# HeadAmp1.net
KiCad netlist of a schematic drawn in EAGLE
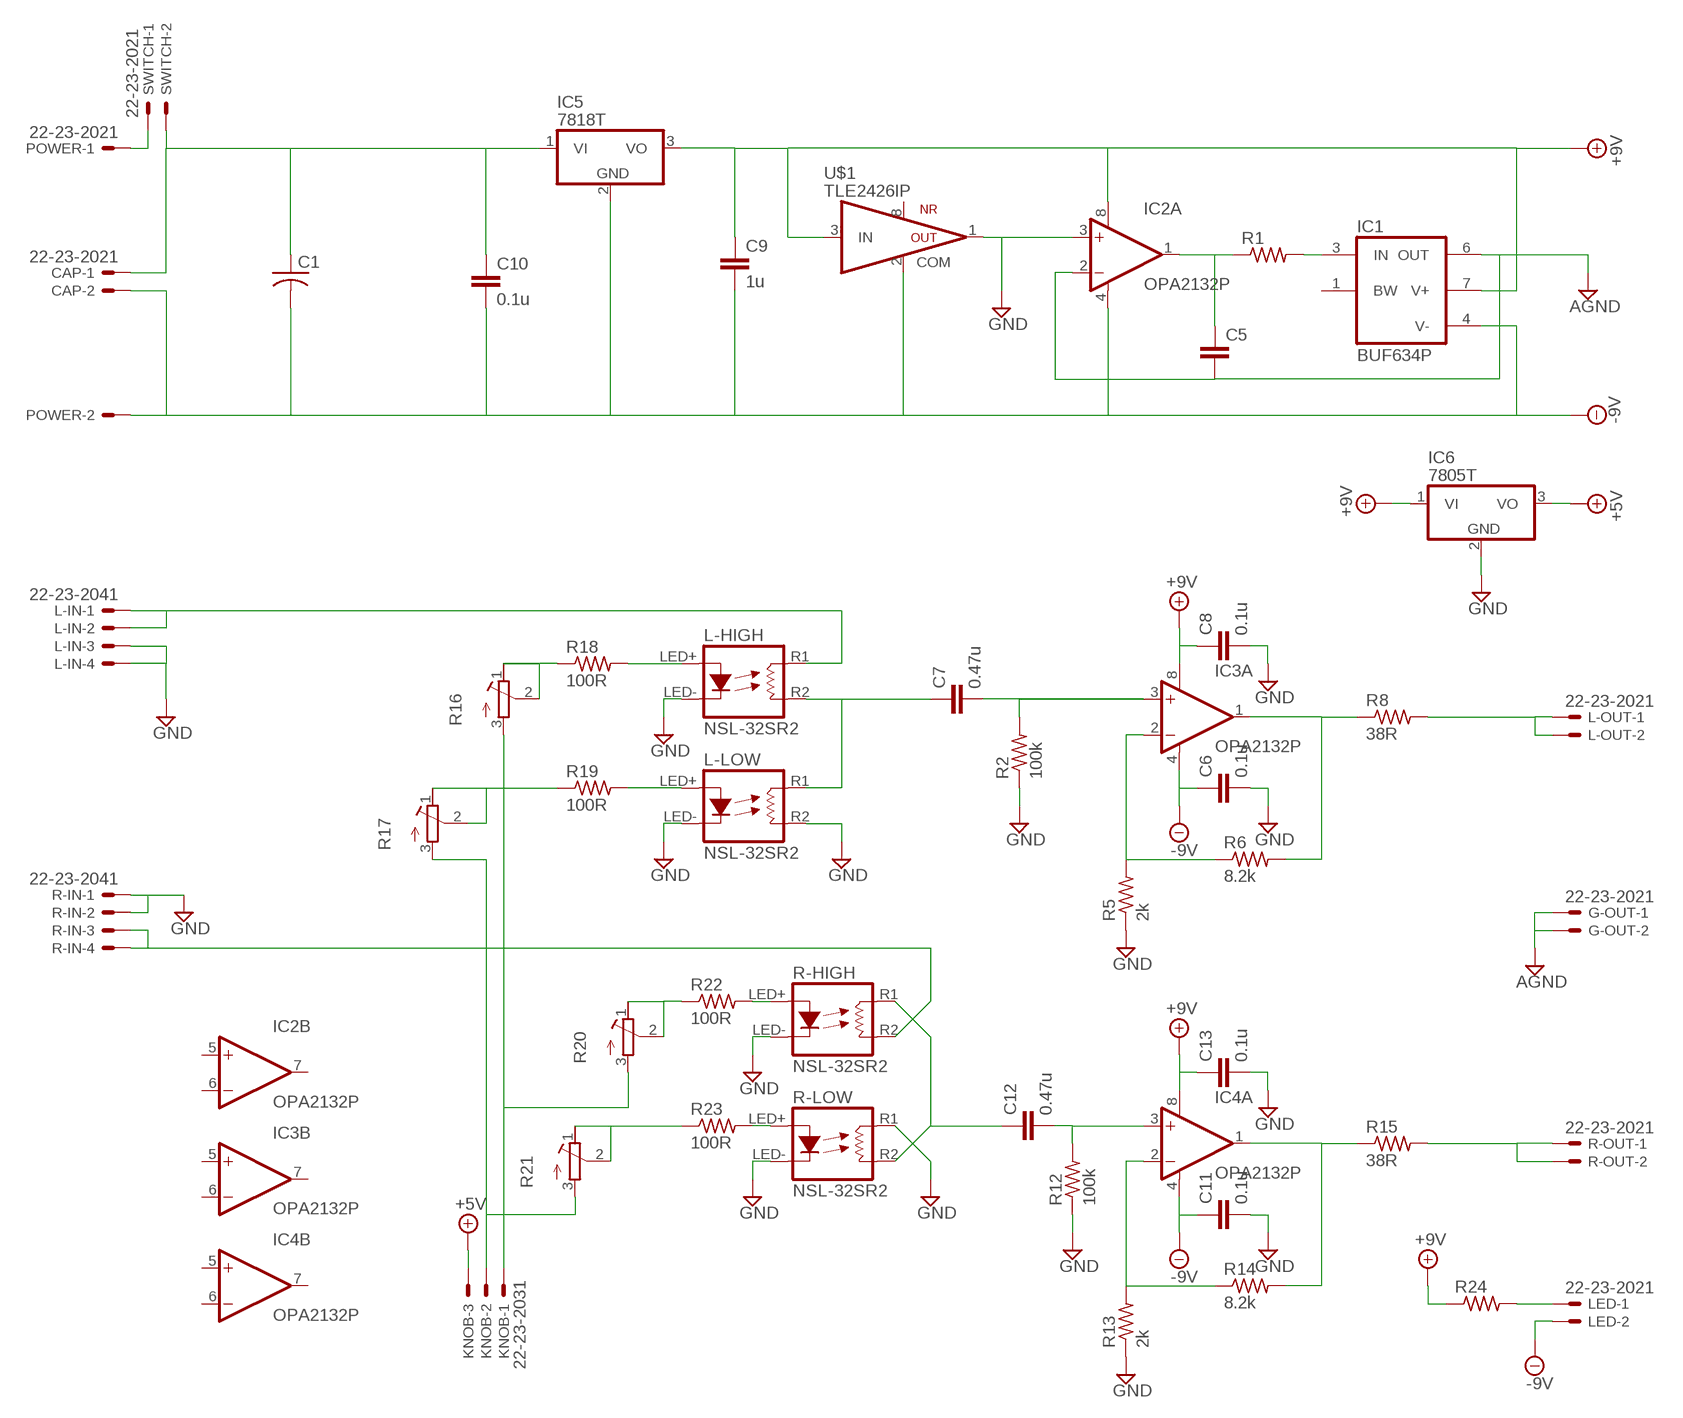
[diagram p0: schematic, sheet 1]

(export (version "E")
  (design (tool "Eeschema 10.0.6"))
  (components
    (comp (ref "C1")
      (value "C-US050-075X075")
      (footprint "eagle-import:C050-075X075")
      (libsource (lib "eagle-import") (part "C-US050-075X075"))
    )
    (comp (ref "C5")
      (value "C5/3")
      (footprint "eagle-import:C5B3")
      (libsource (lib "eagle-import") (part "C5/3"))
    )
    (comp (ref "C6")
      (value "0.1u")
      (footprint "eagle-import:C5B3")
      (libsource (lib "eagle-import") (part "C5/3"))
    )
    (comp (ref "C7")
      (value "0.47u")
      (footprint "eagle-import:C5B3")
      (libsource (lib "eagle-import") (part "C5/3"))
    )
    (comp (ref "C8")
      (value "0.1u")
      (footprint "eagle-import:C5B3")
      (libsource (lib "eagle-import") (part "C5/3"))
    )
    (comp (ref "C9")
      (value "1u")
      (footprint "eagle-import:C5B3")
      (libsource (lib "eagle-import") (part "C5/3"))
    )
    (comp (ref "C10")
      (value "0.1u")
      (footprint "eagle-import:C5B3")
      (libsource (lib "eagle-import") (part "C5/3"))
    )
    (comp (ref "C11")
      (value "0.1u")
      (footprint "eagle-import:C5B3")
      (libsource (lib "eagle-import") (part "C5/3"))
    )
    (comp (ref "C12")
      (value "0.47u")
      (footprint "eagle-import:C5B3")
      (libsource (lib "eagle-import") (part "C5/3"))
    )
    (comp (ref "C13")
      (value "0.1u")
      (footprint "eagle-import:C5B3")
      (libsource (lib "eagle-import") (part "C5/3"))
    )
    (comp (ref "CAP")
      (value "22-23-2021")
      (footprint "eagle-import:22-23-2021")
      (fields (field (name "MF") "MOLEX"))
      (libsource (lib "eagle-import") (part "22-23-2021"))
    )
    (comp (ref "G-OUT")
      (value "22-23-2021")
      (footprint "eagle-import:22-23-2021")
      (fields (field (name "MF") "MOLEX"))
      (libsource (lib "eagle-import") (part "22-23-2021"))
    )
    (comp (ref "IC1")
      (value "BUF634P")
      (footprint "eagle-import:DIL08")
      (fields (field (name "MF") "TEXAS INSTRUMENTS"))
      (libsource (lib "eagle-import") (part "BUF634P"))
    )
    (comp (ref "IC2")
      (value "OPA2132P")
      (footprint "eagle-import:DIL08")
      (libsource (lib "eagle-import") (part "OPA2132P"))
    )
    (comp (ref "IC3")
      (value "OPA2132P")
      (footprint "eagle-import:DIL08")
      (libsource (lib "eagle-import") (part "OPA2132P"))
    )
    (comp (ref "IC4")
      (value "OPA2132P")
      (footprint "eagle-import:DIL08")
      (libsource (lib "eagle-import") (part "OPA2132P"))
    )
    (comp (ref "IC5")
      (value "7818T")
      (footprint "eagle-import:TO220H")
      (libsource (lib "eagle-import") (part "78T18"))
    )
    (comp (ref "IC6")
      (value "7805T")
      (footprint "eagle-import:TO220H")
      (libsource (lib "eagle-import") (part "78T05"))
    )
    (comp (ref "KNOB")
      (value "22-23-2031")
      (footprint "eagle-import:22-23-2031")
      (fields (field (name "MF") "MOLEX"))
      (libsource (lib "eagle-import") (part "22-23-2031"))
    )
    (comp (ref "L-HIGH")
      (value "NSL-32SR2")
      (footprint "eagle-import:OPTO_32SR")
      (libsource (lib "eagle-import") (part "NSL-32SR2"))
    )
    (comp (ref "L-IN")
      (value "22-23-2041")
      (footprint "eagle-import:22-23-2041")
      (fields (field (name "MF") "MOLEX"))
      (libsource (lib "eagle-import") (part "22-23-2041"))
    )
    (comp (ref "L-LOW")
      (value "NSL-32SR2")
      (footprint "eagle-import:OPTO_32SR")
      (libsource (lib "eagle-import") (part "NSL-32SR2"))
    )
    (comp (ref "L-OUT")
      (value "22-23-2021")
      (footprint "eagle-import:22-23-2021")
      (fields (field (name "MF") "MOLEX"))
      (libsource (lib "eagle-import") (part "22-23-2021"))
    )
    (comp (ref "LED")
      (value "22-23-2021")
      (footprint "eagle-import:22-23-2021")
      (fields (field (name "MF") "MOLEX"))
      (libsource (lib "eagle-import") (part "22-23-2021"))
    )
    (comp (ref "POWER")
      (value "22-23-2021")
      (footprint "eagle-import:22-23-2021")
      (fields (field (name "MF") "MOLEX"))
      (libsource (lib "eagle-import") (part "22-23-2021"))
    )
    (comp (ref "R-HIGH")
      (value "NSL-32SR2")
      (footprint "eagle-import:OPTO_32SR")
      (libsource (lib "eagle-import") (part "NSL-32SR2"))
    )
    (comp (ref "R-IN")
      (value "22-23-2041")
      (footprint "eagle-import:22-23-2041")
      (fields (field (name "MF") "MOLEX"))
      (libsource (lib "eagle-import") (part "22-23-2041"))
    )
    (comp (ref "R-LOW")
      (value "NSL-32SR2")
      (footprint "eagle-import:OPTO_32SR")
      (libsource (lib "eagle-import") (part "NSL-32SR2"))
    )
    (comp (ref "R-OUT")
      (value "22-23-2021")
      (footprint "eagle-import:22-23-2021")
      (fields (field (name "MF") "MOLEX"))
      (libsource (lib "eagle-import") (part "22-23-2021"))
    )
    (comp (ref "R1")
      (value "R-US_0207/10")
      (footprint "eagle-import:0207_10")
      (libsource (lib "eagle-import") (part "R-US_0207/10"))
    )
    (comp (ref "R2")
      (value "100k")
      (footprint "eagle-import:0207_10")
      (libsource (lib "eagle-import") (part "R-US_0207/10"))
    )
    (comp (ref "R5")
      (value "2k")
      (footprint "eagle-import:0207_10")
      (libsource (lib "eagle-import") (part "R-US_0207/10"))
    )
    (comp (ref "R6")
      (value "8.2k")
      (footprint "eagle-import:0207_10")
      (libsource (lib "eagle-import") (part "R-US_0207/10"))
    )
    (comp (ref "R8")
      (value "38R")
      (footprint "eagle-import:0207_10")
      (libsource (lib "eagle-import") (part "R-US_0207/10"))
    )
    (comp (ref "R12")
      (value "100k")
      (footprint "eagle-import:0207_10")
      (libsource (lib "eagle-import") (part "R-US_0207/10"))
    )
    (comp (ref "R13")
      (value "2k")
      (footprint "eagle-import:0207_10")
      (libsource (lib "eagle-import") (part "R-US_0207/10"))
    )
    (comp (ref "R14")
      (value "8.2k")
      (footprint "eagle-import:0207_10")
      (libsource (lib "eagle-import") (part "R-US_0207/10"))
    )
    (comp (ref "R15")
      (value "38R")
      (footprint "eagle-import:0207_10")
      (libsource (lib "eagle-import") (part "R-US_0207/10"))
    )
    (comp (ref "R16")
      (value "R-TRIMMT93YB")
      (footprint "eagle-import:RTRIMT93YB")
      (libsource (lib "eagle-import") (part "R-TRIMMT93YB"))
    )
    (comp (ref "R17")
      (value "R-TRIMMT93YB")
      (footprint "eagle-import:RTRIMT93YB")
      (libsource (lib "eagle-import") (part "R-TRIMMT93YB"))
    )
    (comp (ref "R18")
      (value "100R")
      (footprint "eagle-import:0207_10")
      (libsource (lib "eagle-import") (part "R-US_0207/10"))
    )
    (comp (ref "R19")
      (value "100R")
      (footprint "eagle-import:0207_10")
      (libsource (lib "eagle-import") (part "R-US_0207/10"))
    )
    (comp (ref "R20")
      (value "R-TRIMMT93YB")
      (footprint "eagle-import:RTRIMT93YB")
      (libsource (lib "eagle-import") (part "R-TRIMMT93YB"))
    )
    (comp (ref "R21")
      (value "R-TRIMMT93YB")
      (footprint "eagle-import:RTRIMT93YB")
      (libsource (lib "eagle-import") (part "R-TRIMMT93YB"))
    )
    (comp (ref "R22")
      (value "100R")
      (footprint "eagle-import:0207_10")
      (libsource (lib "eagle-import") (part "R-US_0207/10"))
    )
    (comp (ref "R23")
      (value "100R")
      (footprint "eagle-import:0207_10")
      (libsource (lib "eagle-import") (part "R-US_0207/10"))
    )
    (comp (ref "R24")
      (value "R-US_0207/10")
      (footprint "eagle-import:0207_10")
      (libsource (lib "eagle-import") (part "R-US_0207/10"))
    )
    (comp (ref "SWITCH")
      (value "22-23-2021")
      (footprint "eagle-import:22-23-2021")
      (fields (field (name "MF") "MOLEX"))
      (libsource (lib "eagle-import") (part "22-23-2021"))
    )
    (comp (ref "U$1")
      (value "TLE2426IP")
      (footprint "eagle-import:DIL08")
      (libsource (lib "eagle-import") (part "TLE2426IP"))
    )
  )
  (nets
    (net (code "1") (name "+5V") (class "Default")
      (node (ref "IC6") (pin "3") (pinfunction "VO_3") (pintype "passive"))
      (node (ref "KNOB") (pin "3") (pinfunction "S_3") (pintype "passive"))
    )
    (net (code "2") (name "+9V") (class "Default")
      (node (ref "C13") (pin "1") (pinfunction "1_1") (pintype "passive"))
      (node (ref "C8") (pin "1") (pinfunction "1_1") (pintype "passive"))
      (node (ref "C9") (pin "1") (pinfunction "1_1") (pintype "passive"))
      (node (ref "IC1") (pin "7") (pinfunction "V+_7") (pintype "power_in"))
      (node (ref "IC2") (pin "8") (pinfunction "V+_8") (pintype "power_in"))
      (node (ref "IC3") (pin "8") (pinfunction "V+_8") (pintype "power_in"))
      (node (ref "IC4") (pin "8") (pinfunction "V+_8") (pintype "power_in"))
      (node (ref "IC5") (pin "3") (pinfunction "VO_3") (pintype "passive"))
      (node (ref "IC6") (pin "1") (pinfunction "VI_1") (pintype "input"))
      (node (ref "R24") (pin "1") (pinfunction "1_1") (pintype "passive"))
      (node (ref "U$1") (pin "3") (pinfunction "IN_3") (pintype "input"))
    )
    (net (code "3") (name "-9V") (class "Default")
      (node (ref "C1") (pin "2") (pinfunction "2_2") (pintype "passive"))
      (node (ref "C10") (pin "2") (pinfunction "2_2") (pintype "passive"))
      (node (ref "C11") (pin "1") (pinfunction "1_1") (pintype "passive"))
      (node (ref "C6") (pin "1") (pinfunction "1_1") (pintype "passive"))
      (node (ref "C9") (pin "2") (pinfunction "2_2") (pintype "passive"))
      (node (ref "CAP") (pin "2") (pinfunction "S_2") (pintype "passive"))
      (node (ref "IC1") (pin "4") (pinfunction "V-_4") (pintype "power_in"))
      (node (ref "IC2") (pin "4") (pinfunction "V-_4") (pintype "power_in"))
      (node (ref "IC3") (pin "4") (pinfunction "V-_4") (pintype "power_in"))
      (node (ref "IC4") (pin "4") (pinfunction "V-_4") (pintype "power_in"))
      (node (ref "IC5") (pin "2") (pinfunction "GND_2") (pintype "passive"))
      (node (ref "LED") (pin "2") (pinfunction "S_2") (pintype "passive"))
      (node (ref "POWER") (pin "2") (pinfunction "S_2") (pintype "passive"))
      (node (ref "U$1") (pin "2") (pinfunction "COMMON_2") (pintype "passive"))
    )
    (net (code "4") (name "AGND") (class "Default")
      (node (ref "C5") (pin "2") (pinfunction "2_2") (pintype "passive"))
      (node (ref "G-OUT") (pin "1") (pinfunction "S_1") (pintype "passive"))
      (node (ref "G-OUT") (pin "2") (pinfunction "S_2") (pintype "passive"))
      (node (ref "IC1") (pin "6") (pinfunction "OUT_6") (pintype "output"))
      (node (ref "IC2") (pin "2") (pinfunction "-IN_2") (pintype "input"))
    )
    (net (code "5") (name "GND") (class "Default")
      (node (ref "C11") (pin "2") (pinfunction "2_2") (pintype "passive"))
      (node (ref "C13") (pin "2") (pinfunction "2_2") (pintype "passive"))
      (node (ref "C6") (pin "2") (pinfunction "2_2") (pintype "passive"))
      (node (ref "C8") (pin "2") (pinfunction "2_2") (pintype "passive"))
      (node (ref "IC2") (pin "3") (pinfunction "+IN_3") (pintype "input"))
      (node (ref "IC6") (pin "2") (pinfunction "GND_2") (pintype "passive"))
      (node (ref "L-HIGH") (pin "LED-") (pinfunction "C_LED-") (pintype "passive"))
      (node (ref "L-IN") (pin "3") (pinfunction "S_3") (pintype "passive"))
      (node (ref "L-IN") (pin "4") (pinfunction "S_4") (pintype "passive"))
      (node (ref "L-LOW") (pin "LED-") (pinfunction "C_LED-") (pintype "passive"))
      (node (ref "L-LOW") (pin "R2") (pinfunction "L2_R2") (pintype "passive"))
      (node (ref "R-HIGH") (pin "LED-") (pinfunction "C_LED-") (pintype "passive"))
      (node (ref "R-IN") (pin "1") (pinfunction "S_1") (pintype "passive"))
      (node (ref "R-IN") (pin "2") (pinfunction "S_2") (pintype "passive"))
      (node (ref "R-LOW") (pin "LED-") (pinfunction "C_LED-") (pintype "passive"))
      (node (ref "R-LOW") (pin "R1") (pinfunction "L1_R1") (pintype "passive"))
      (node (ref "R12") (pin "1") (pinfunction "1_1") (pintype "passive"))
      (node (ref "R13") (pin "1") (pinfunction "1_1") (pintype "passive"))
      (node (ref "R2") (pin "1") (pinfunction "1_1") (pintype "passive"))
      (node (ref "R5") (pin "1") (pinfunction "1_1") (pintype "passive"))
      (node (ref "U$1") (pin "1") (pinfunction "OUT_1") (pintype "passive"))
    )
    (net (code "6") (name "Net-(CAPA-S)") (class "Default")
      (node (ref "C1") (pin "1") (pinfunction "1_1") (pintype "passive"))
      (node (ref "C10") (pin "1") (pinfunction "1_1") (pintype "passive"))
      (node (ref "CAP") (pin "1") (pinfunction "S_1") (pintype "passive"))
      (node (ref "IC5") (pin "1") (pinfunction "VI_1") (pintype "input"))
      (node (ref "SWITCH") (pin "2") (pinfunction "S_2") (pintype "passive"))
    )
    (net (code "7") (name "Net-(IC1-IN)") (class "Default")
      (node (ref "IC1") (pin "3") (pinfunction "IN_3") (pintype "input"))
      (node (ref "R1") (pin "2") (pinfunction "2_2") (pintype "passive"))
    )
    (net (code "8") (name "Net-(IC2A-OUT)") (class "Default")
      (node (ref "C5") (pin "1") (pinfunction "1_1") (pintype "passive"))
      (node (ref "IC2") (pin "1") (pinfunction "OUT_1") (pintype "output"))
      (node (ref "R1") (pin "1") (pinfunction "1_1") (pintype "passive"))
    )
    (net (code "9") (name "Net-(IC3A-+IN)") (class "Default")
      (node (ref "C7") (pin "2") (pinfunction "2_2") (pintype "passive"))
      (node (ref "IC3") (pin "3") (pinfunction "+IN_3") (pintype "input"))
      (node (ref "R2") (pin "2") (pinfunction "2_2") (pintype "passive"))
    )
    (net (code "10") (name "Net-(IC3A--IN)") (class "Default")
      (node (ref "IC3") (pin "2") (pinfunction "-IN_2") (pintype "input"))
      (node (ref "R5") (pin "2") (pinfunction "2_2") (pintype "passive"))
      (node (ref "R6") (pin "1") (pinfunction "1_1") (pintype "passive"))
    )
    (net (code "11") (name "Net-(IC3A-OUT)") (class "Default")
      (node (ref "IC3") (pin "1") (pinfunction "OUT_1") (pintype "output"))
      (node (ref "R6") (pin "2") (pinfunction "2_2") (pintype "passive"))
      (node (ref "R8") (pin "1") (pinfunction "1_1") (pintype "passive"))
    )
    (net (code "12") (name "Net-(IC4A-+IN)") (class "Default")
      (node (ref "C12") (pin "2") (pinfunction "2_2") (pintype "passive"))
      (node (ref "IC4") (pin "3") (pinfunction "+IN_3") (pintype "input"))
      (node (ref "R12") (pin "2") (pinfunction "2_2") (pintype "passive"))
    )
    (net (code "13") (name "Net-(IC4A--IN)") (class "Default")
      (node (ref "IC4") (pin "2") (pinfunction "-IN_2") (pintype "input"))
      (node (ref "R13") (pin "2") (pinfunction "2_2") (pintype "passive"))
      (node (ref "R14") (pin "1") (pinfunction "1_1") (pintype "passive"))
    )
    (net (code "14") (name "Net-(IC4A-OUT)") (class "Default")
      (node (ref "IC4") (pin "1") (pinfunction "OUT_1") (pintype "output"))
      (node (ref "R14") (pin "2") (pinfunction "2_2") (pintype "passive"))
      (node (ref "R15") (pin "1") (pinfunction "1_1") (pintype "passive"))
    )
    (net (code "15") (name "Net-(KNOBA-S)") (class "Default")
      (node (ref "KNOB") (pin "1") (pinfunction "S_1") (pintype "passive"))
      (node (ref "R16") (pin "3") (pinfunction "E_3") (pintype "passive"))
      (node (ref "R20") (pin "3") (pinfunction "E_3") (pintype "passive"))
    )
    (net (code "16") (name "Net-(KNOBB-S)") (class "Default")
      (node (ref "KNOB") (pin "2") (pinfunction "S_2") (pintype "passive"))
      (node (ref "R17") (pin "3") (pinfunction "E_3") (pintype "passive"))
      (node (ref "R21") (pin "3") (pinfunction "E_3") (pintype "passive"))
    )
    (net (code "17") (name "Net-(L-HIGH-A)") (class "Default")
      (node (ref "L-HIGH") (pin "LED+") (pinfunction "A_LED+") (pintype "passive"))
      (node (ref "R18") (pin "2") (pinfunction "2_2") (pintype "passive"))
    )
    (net (code "18") (name "Net-(L-HIGH-L1)") (class "Default")
      (node (ref "L-HIGH") (pin "R1") (pinfunction "L1_R1") (pintype "passive"))
      (node (ref "L-IN") (pin "1") (pinfunction "S_1") (pintype "passive"))
      (node (ref "L-IN") (pin "2") (pinfunction "S_2") (pintype "passive"))
    )
    (net (code "19") (name "Net-(L-HIGH-L2)") (class "Default")
      (node (ref "C7") (pin "1") (pinfunction "1_1") (pintype "passive"))
      (node (ref "L-HIGH") (pin "R2") (pinfunction "L2_R2") (pintype "passive"))
      (node (ref "L-LOW") (pin "R1") (pinfunction "L1_R1") (pintype "passive"))
    )
    (net (code "20") (name "Net-(L-LOW-A)") (class "Default")
      (node (ref "L-LOW") (pin "LED+") (pinfunction "A_LED+") (pintype "passive"))
      (node (ref "R19") (pin "2") (pinfunction "2_2") (pintype "passive"))
    )
    (net (code "21") (name "Net-(L-OUTA-S)") (class "Default")
      (node (ref "L-OUT") (pin "1") (pinfunction "S_1") (pintype "passive"))
      (node (ref "L-OUT") (pin "2") (pinfunction "S_2") (pintype "passive"))
      (node (ref "R8") (pin "2") (pinfunction "2_2") (pintype "passive"))
    )
    (net (code "22") (name "Net-(LEDA-S)") (class "Default")
      (node (ref "LED") (pin "1") (pinfunction "S_1") (pintype "passive"))
      (node (ref "R24") (pin "2") (pinfunction "2_2") (pintype "passive"))
    )
    (net (code "23") (name "Net-(POWERA-S)") (class "Default")
      (node (ref "POWER") (pin "1") (pinfunction "S_1") (pintype "passive"))
      (node (ref "SWITCH") (pin "1") (pinfunction "S_1") (pintype "passive"))
    )
    (net (code "24") (name "Net-(R-HIGH-A)") (class "Default")
      (node (ref "R-HIGH") (pin "LED+") (pinfunction "A_LED+") (pintype "passive"))
      (node (ref "R22") (pin "2") (pinfunction "2_2") (pintype "passive"))
    )
    (net (code "25") (name "Net-(R-HIGH-L1)") (class "Default")
      (node (ref "C12") (pin "1") (pinfunction "1_1") (pintype "passive"))
      (node (ref "R-HIGH") (pin "R1") (pinfunction "L1_R1") (pintype "passive"))
      (node (ref "R-LOW") (pin "R2") (pinfunction "L2_R2") (pintype "passive"))
    )
    (net (code "26") (name "Net-(R-HIGH-L2)") (class "Default")
      (node (ref "R-HIGH") (pin "R2") (pinfunction "L2_R2") (pintype "passive"))
      (node (ref "R-IN") (pin "3") (pinfunction "S_3") (pintype "passive"))
      (node (ref "R-IN") (pin "4") (pinfunction "S_4") (pintype "passive"))
    )
    (net (code "27") (name "Net-(R-LOW-A)") (class "Default")
      (node (ref "R-LOW") (pin "LED+") (pinfunction "A_LED+") (pintype "passive"))
      (node (ref "R23") (pin "2") (pinfunction "2_2") (pintype "passive"))
    )
    (net (code "28") (name "Net-(R-OUTA-S)") (class "Default")
      (node (ref "R-OUT") (pin "1") (pinfunction "S_1") (pintype "passive"))
      (node (ref "R-OUT") (pin "2") (pinfunction "S_2") (pintype "passive"))
      (node (ref "R15") (pin "2") (pinfunction "2_2") (pintype "passive"))
    )
    (net (code "29") (name "Net-(R16-A)") (class "Default")
      (node (ref "R16") (pin "1") (pinfunction "A_1") (pintype "passive"))
      (node (ref "R16") (pin "2") (pinfunction "S_2") (pintype "passive"))
      (node (ref "R18") (pin "1") (pinfunction "1_1") (pintype "passive"))
    )
    (net (code "30") (name "Net-(R17-A)") (class "Default")
      (node (ref "R17") (pin "1") (pinfunction "A_1") (pintype "passive"))
      (node (ref "R17") (pin "2") (pinfunction "S_2") (pintype "passive"))
      (node (ref "R19") (pin "1") (pinfunction "1_1") (pintype "passive"))
    )
    (net (code "31") (name "Net-(R20-A)") (class "Default")
      (node (ref "R20") (pin "1") (pinfunction "A_1") (pintype "passive"))
      (node (ref "R20") (pin "2") (pinfunction "S_2") (pintype "passive"))
      (node (ref "R22") (pin "1") (pinfunction "1_1") (pintype "passive"))
    )
    (net (code "32") (name "Net-(R21-A)") (class "Default")
      (node (ref "R21") (pin "1") (pinfunction "A_1") (pintype "passive"))
      (node (ref "R21") (pin "2") (pinfunction "S_2") (pintype "passive"))
      (node (ref "R23") (pin "1") (pinfunction "1_1") (pintype "passive"))
    )
    (net (code "33") (name "unconnected-(IC1-BW-Pad1)") (class "Default")
      (node (ref "IC1") (pin "1") (pinfunction "BW_1") (pintype "passive"))
    )
    (net (code "34") (name "unconnected-(IC2B-+IN-Pad5)") (class "Default")
      (node (ref "IC2") (pin "5") (pinfunction "+IN_5") (pintype "input"))
    )
    (net (code "35") (name "unconnected-(IC2B--IN-Pad6)") (class "Default")
      (node (ref "IC2") (pin "6") (pinfunction "-IN_6") (pintype "input"))
    )
    (net (code "36") (name "unconnected-(IC2B-OUT-Pad7)") (class "Default")
      (node (ref "IC2") (pin "7") (pinfunction "OUT_7") (pintype "output"))
    )
    (net (code "37") (name "unconnected-(IC3B-+IN-Pad5)") (class "Default")
      (node (ref "IC3") (pin "5") (pinfunction "+IN_5") (pintype "input"))
    )
    (net (code "38") (name "unconnected-(IC3B--IN-Pad6)") (class "Default")
      (node (ref "IC3") (pin "6") (pinfunction "-IN_6") (pintype "input"))
    )
    (net (code "39") (name "unconnected-(IC3B-OUT-Pad7)") (class "Default")
      (node (ref "IC3") (pin "7") (pinfunction "OUT_7") (pintype "output"))
    )
    (net (code "40") (name "unconnected-(IC4B-+IN-Pad5)") (class "Default")
      (node (ref "IC4") (pin "5") (pinfunction "+IN_5") (pintype "input"))
    )
    (net (code "41") (name "unconnected-(IC4B--IN-Pad6)") (class "Default")
      (node (ref "IC4") (pin "6") (pinfunction "-IN_6") (pintype "input"))
    )
    (net (code "42") (name "unconnected-(IC4B-OUT-Pad7)") (class "Default")
      (node (ref "IC4") (pin "7") (pinfunction "OUT_7") (pintype "output"))
    )
    (net (code "43") (name "unconnected-(U$1-NR-Pad8)") (class "Default")
      (node (ref "U$1") (pin "8") (pinfunction "NR_8") (pintype "bidirectional"))
    )
  )
)
